# DMXTX.net
KiCad netlist of a schematic drawn in EAGLE
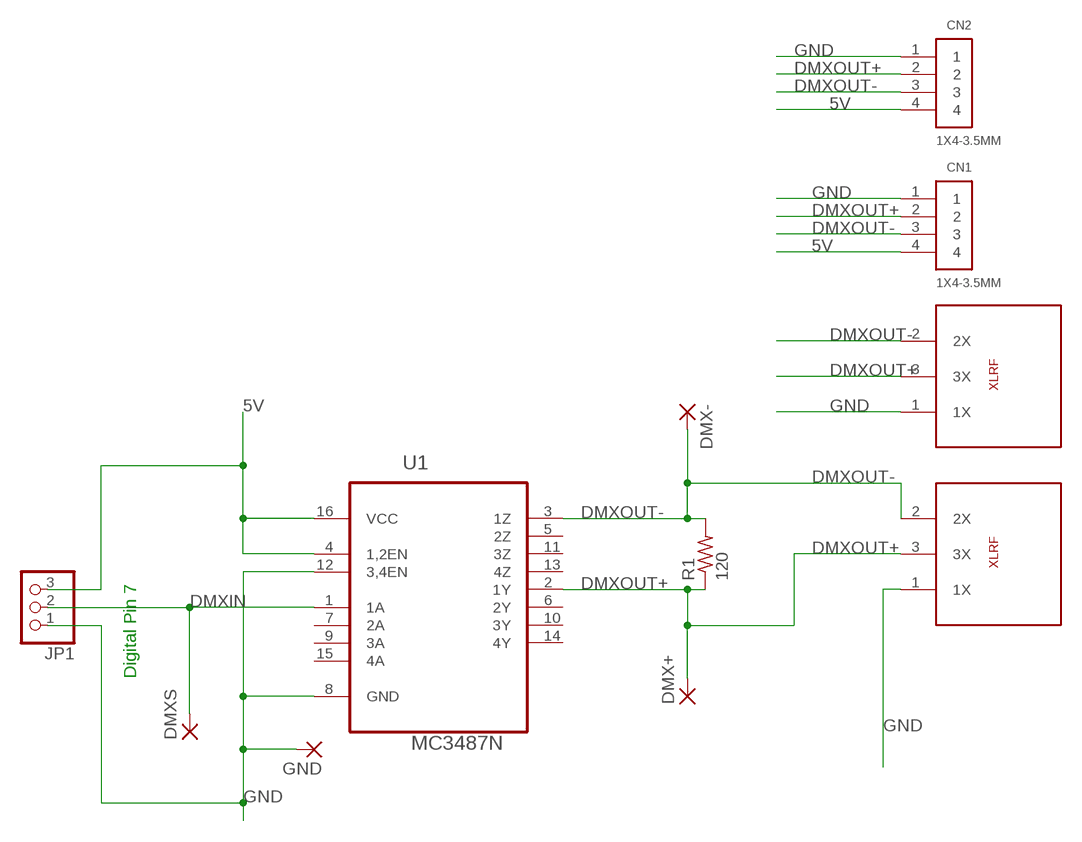
[diagram p0: schematic, sheet 1]

(export (version "E")
  (design (tool "Eeschema 10.0.6"))
  (components
    (comp (ref "CN1")
      (value "1X4-3.5MM")
      (footprint "eagle-import:1X04-3.5MM")
      (libsource (lib "eagle-import") (part "1X4-3.5MM"))
    )
    (comp (ref "CN2")
      (value "1X4-3.5MM")
      (footprint "eagle-import:1X04-3.5MM")
      (libsource (lib "eagle-import") (part "1X4-3.5MM"))
    )
    (comp (ref "DMX+")
      (value "3,81/1,4")
      (footprint "eagle-import:3,81_1,4")
      (libsource (lib "eagle-import") (part "3,81/1,4"))
    )
    (comp (ref "DMX-")
      (value "3,81/1,4")
      (footprint "eagle-import:3,81_1,4")
      (libsource (lib "eagle-import") (part "3,81/1,4"))
    )
    (comp (ref "DMXS")
      (value "3,81/1,4")
      (footprint "eagle-import:3,81_1,4")
      (libsource (lib "eagle-import") (part "3,81/1,4"))
    )
    (comp (ref "GND")
      (value "3,81/1,4")
      (footprint "eagle-import:3,81_1,4")
      (libsource (lib "eagle-import") (part "3,81/1,4"))
    )
    (comp (ref "JP1")
      (value "PINHD-1X3")
      (footprint "eagle-import:1X03")
      (libsource (lib "eagle-import") (part "PINHD-1X3"))
    )
    (comp (ref "R1")
      (value "120")
      (footprint "eagle-import:0414_15")
      (libsource (lib "eagle-import") (part "R-US_0414/15"))
    )
    (comp (ref "U$1")
      (value "XLRCONNECTOR")
      (footprint "eagle-import:DMXF3PIN")
      (libsource (lib "eagle-import") (part "XLRCONNECTOR"))
    )
    (comp (ref "U$2")
      (value "XLRCONNECTOR")
      (footprint "eagle-import:DMXF3PIN")
      (libsource (lib "eagle-import") (part "XLRCONNECTOR"))
    )
    (comp (ref "U1")
      (value "MC3487N")
      (footprint "eagle-import:DIP254P762X508-16")
      (libsource (lib "eagle-import") (part "MC3487N"))
    )
  )
  (nets
    (net (code "1") (name "/5V") (class "Default")
      (node (ref "CN1") (pin "4") (pinfunction "4_4") (pintype "bidirectional"))
      (node (ref "CN2") (pin "4") (pinfunction "4_4") (pintype "bidirectional"))
      (node (ref "JP1") (pin "3") (pinfunction "3_3") (pintype "passive"))
      (node (ref "U1") (pin "16") (pinfunction "VCC_16") (pintype "power_in"))
      (node (ref "U1") (pin "4") (pinfunction "1,2EN_4") (pintype "input"))
    )
    (net (code "2") (name "/DMXIN") (class "Default")
      (node (ref "DMXS") (pin "1") (pinfunction "P_1") (pintype "passive"))
      (node (ref "JP1") (pin "2") (pinfunction "2_2") (pintype "passive"))
      (node (ref "U1") (pin "1") (pinfunction "1A_1") (pintype "input"))
    )
    (net (code "3") (name "/DMXOUT+") (class "Default")
      (node (ref "CN1") (pin "2") (pinfunction "2_2") (pintype "bidirectional"))
      (node (ref "CN2") (pin "2") (pinfunction "2_2") (pintype "bidirectional"))
      (node (ref "DMX+") (pin "1") (pinfunction "P_1") (pintype "passive"))
      (node (ref "R1") (pin "1") (pinfunction "1_1") (pintype "passive"))
      (node (ref "U$1") (pin "3") (pinfunction "3X_3") (pintype "bidirectional"))
      (node (ref "U$2") (pin "3") (pinfunction "3X_3") (pintype "bidirectional"))
      (node (ref "U1") (pin "2") (pinfunction "1Y_2") (pintype "output"))
    )
    (net (code "4") (name "/DMXOUT-") (class "Default")
      (node (ref "CN1") (pin "3") (pinfunction "3_3") (pintype "bidirectional"))
      (node (ref "CN2") (pin "3") (pinfunction "3_3") (pintype "bidirectional"))
      (node (ref "DMX-") (pin "1") (pinfunction "P_1") (pintype "passive"))
      (node (ref "R1") (pin "2") (pinfunction "2_2") (pintype "passive"))
      (node (ref "U$1") (pin "2") (pinfunction "2X_2") (pintype "bidirectional"))
      (node (ref "U$2") (pin "2") (pinfunction "2X_2") (pintype "bidirectional"))
      (node (ref "U1") (pin "3") (pinfunction "1Z_3") (pintype "output"))
    )
    (net (code "5") (name "/GND") (class "Default")
      (node (ref "CN1") (pin "1") (pinfunction "1_1") (pintype "bidirectional"))
      (node (ref "CN2") (pin "1") (pinfunction "1_1") (pintype "bidirectional"))
      (node (ref "GND") (pin "1") (pinfunction "P_1") (pintype "passive"))
      (node (ref "JP1") (pin "1") (pinfunction "1_1") (pintype "passive"))
      (node (ref "U$1") (pin "1") (pinfunction "1X_1") (pintype "bidirectional"))
      (node (ref "U$2") (pin "1") (pinfunction "1X_1") (pintype "bidirectional"))
      (node (ref "U1") (pin "12") (pinfunction "3,4EN_12") (pintype "input"))
      (node (ref "U1") (pin "8") (pinfunction "GND_8") (pintype "passive"))
    )
    (net (code "6") (name "unconnected-(U1-2A-Pad7)") (class "Default")
      (node (ref "U1") (pin "7") (pinfunction "2A_7") (pintype "input"))
    )
    (net (code "7") (name "unconnected-(U1-2Y-Pad6)") (class "Default")
      (node (ref "U1") (pin "6") (pinfunction "2Y_6") (pintype "output"))
    )
    (net (code "8") (name "unconnected-(U1-2Z-Pad5)") (class "Default")
      (node (ref "U1") (pin "5") (pinfunction "2Z_5") (pintype "output"))
    )
    (net (code "9") (name "unconnected-(U1-3A-Pad9)") (class "Default")
      (node (ref "U1") (pin "9") (pinfunction "3A_9") (pintype "input"))
    )
    (net (code "10") (name "unconnected-(U1-3Y-Pad10)") (class "Default")
      (node (ref "U1") (pin "10") (pinfunction "3Y_10") (pintype "output"))
    )
    (net (code "11") (name "unconnected-(U1-3Z-Pad11)") (class "Default")
      (node (ref "U1") (pin "11") (pinfunction "3Z_11") (pintype "output"))
    )
    (net (code "12") (name "unconnected-(U1-4A-Pad15)") (class "Default")
      (node (ref "U1") (pin "15") (pinfunction "4A_15") (pintype "input"))
    )
    (net (code "13") (name "unconnected-(U1-4Y-Pad14)") (class "Default")
      (node (ref "U1") (pin "14") (pinfunction "4Y_14") (pintype "output"))
    )
    (net (code "14") (name "unconnected-(U1-4Z-Pad13)") (class "Default")
      (node (ref "U1") (pin "13") (pinfunction "4Z_13") (pintype "output"))
    )
  )
)
